# downmixersB.net
KiCad netlist of a schematic drawn in Altium Designer
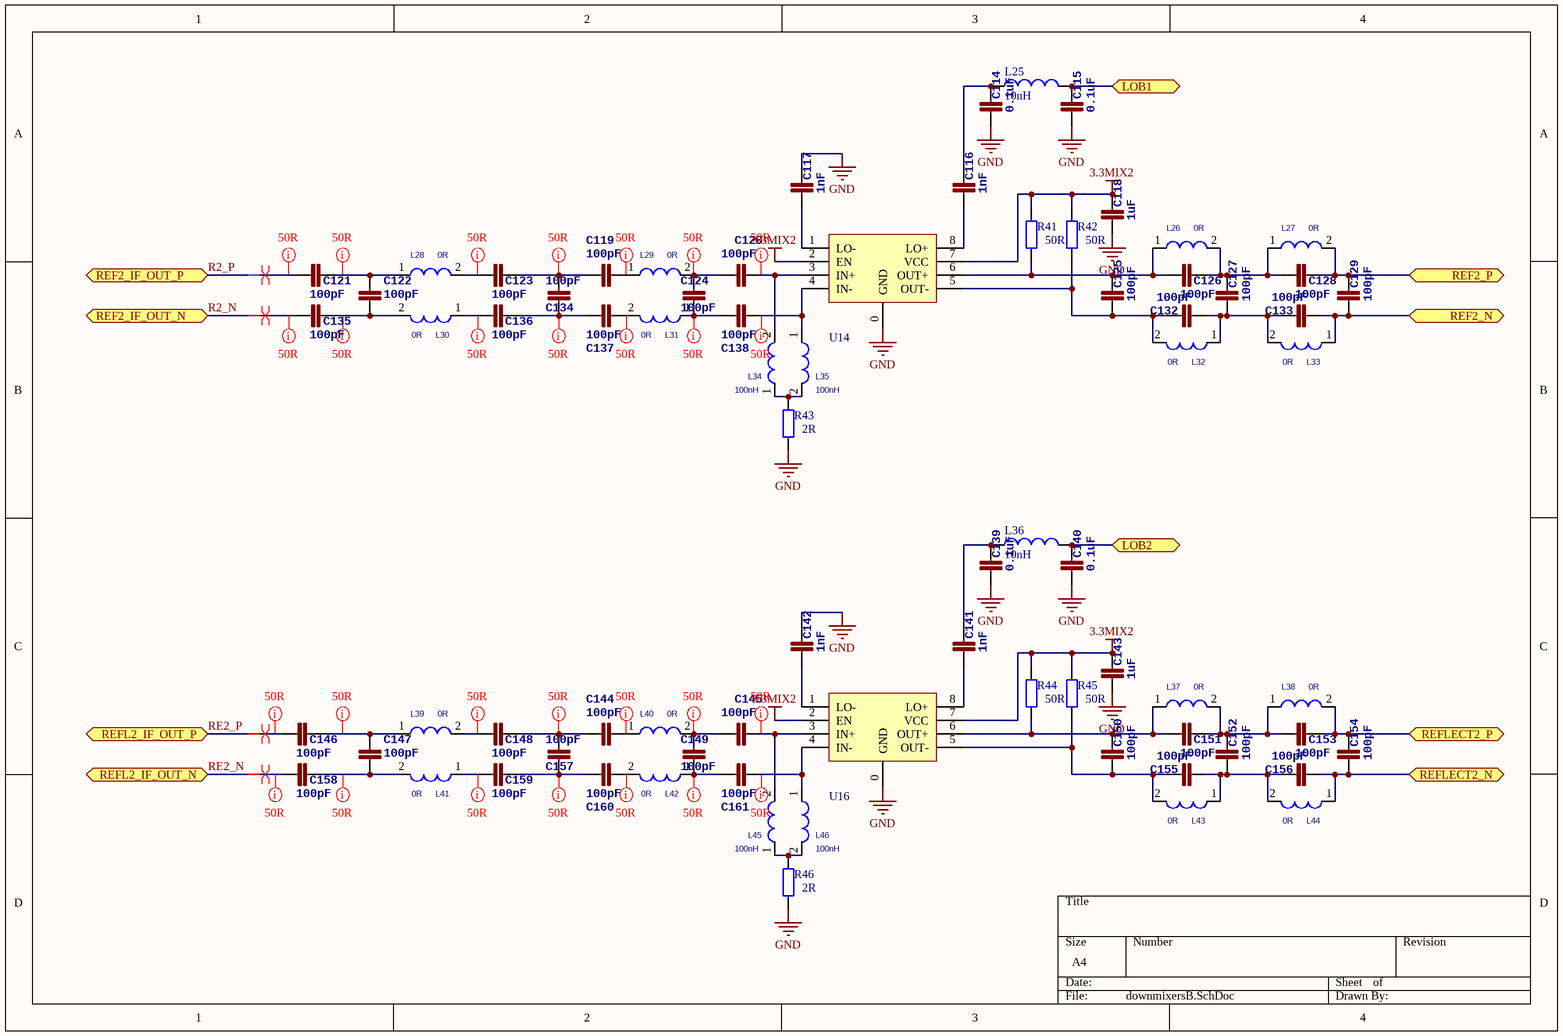
[diagram p0: downmixersB.SchDoc]

(export (version "E")
  (design (tool "Eeschema 10.0.6"))
  (components
    (comp (ref "C114")
      (value "0.1uF")
      (footprint "0402")
      (description "<b>Capacitor</b>\nStandard 0603 ceramic capacitor, and 0.1\" leaded capacitor.")
      (fields (field (name "PARTNO") "CC0402ZRY5V7BB104"))
      (libsource (lib "pixhawk2") (part "CAP0402-CAP"))
    )
    (comp (ref "C115")
      (value "0.1uF")
      (footprint "0402")
      (description "<b>Capacitor</b>\nStandard 0603 ceramic capacitor, and 0.1\" leaded capacitor.")
      (fields (field (name "PARTNO") "CC0402ZRY5V7BB104"))
      (libsource (lib "pixhawk2") (part "CAP0402-CAP"))
    )
    (comp (ref "C116")
      (value "1nF")
      (footprint "0402")
      (description "<b>Capacitor</b>\nStandard 0603 ceramic capacitor, and 0.1\" leaded capacitor.")
      (fields (field (name "PARTNO") "CC0402ZRY5V7BB104"))
      (libsource (lib "pixhawk2") (part "CAP0402-CAP"))
    )
    (comp (ref "C117")
      (value "1nF")
      (footprint "0402")
      (description "<b>Capacitor</b>\nStandard 0603 ceramic capacitor, and 0.1\" leaded capacitor.")
      (fields (field (name "PARTNO") "CC0402ZRY5V7BB104"))
      (libsource (lib "pixhawk2") (part "CAP0402-CAP"))
    )
    (comp (ref "C118")
      (value "1uF")
      (footprint "0402")
      (description "<b>Capacitor</b>\nStandard 0603 ceramic capacitor, and 0.1\" leaded capacitor.")
      (fields (field (name "PARTNO") "CC0402ZRY5V7BB104"))
      (libsource (lib "pixhawk2") (part "CAP0402-CAP"))
    )
    (comp (ref "C119")
      (value "100pF")
      (footprint "0402")
      (description "<b>Capacitor</b>\nStandard 0603 ceramic capacitor, and 0.1\" leaded capacitor.")
      (fields (field (name "PARTNO") "CC0402ZRY5V7BB104"))
      (libsource (lib "") (part "CAP0402-CAP_2"))
    )
    (comp (ref "C120")
      (value "100pF")
      (footprint "0402")
      (description "<b>Capacitor</b>\nStandard 0603 ceramic capacitor, and 0.1\" leaded capacitor.")
      (fields (field (name "PARTNO") "CC0402ZRY5V7BB104"))
      (libsource (lib "") (part "CAP0402-CAP_2"))
    )
    (comp (ref "C121")
      (value "100pF")
      (footprint "0402")
      (description "<b>Capacitor</b>\nStandard 0603 ceramic capacitor, and 0.1\" leaded capacitor.")
      (fields (field (name "PARTNO") "CC0402ZRY5V7BB104"))
      (libsource (lib "") (part "CAP0402-CAP_2"))
    )
    (comp (ref "C122")
      (value "100pF")
      (footprint "0402")
      (description "<b>Capacitor</b>\nStandard 0603 ceramic capacitor, and 0.1\" leaded capacitor.")
      (fields (field (name "PARTNO") "CC0402ZRY5V7BB104"))
      (libsource (lib "pixhawk2") (part "CAP0402-CAP"))
    )
    (comp (ref "C123")
      (value "100pF")
      (footprint "0402")
      (description "<b>Capacitor</b>\nStandard 0603 ceramic capacitor, and 0.1\" leaded capacitor.")
      (fields (field (name "PARTNO") "CC0402ZRY5V7BB104"))
      (libsource (lib "") (part "CAP0402-CAP_2"))
    )
    (comp (ref "C124")
      (value "100pF")
      (footprint "0402")
      (description "<b>Capacitor</b>\nStandard 0603 ceramic capacitor, and 0.1\" leaded capacitor.")
      (fields (field (name "PARTNO") "CC0402ZRY5V7BB104"))
      (libsource (lib "pixhawk2") (part "CAP0402-CAP"))
    )
    (comp (ref "C125")
      (value "100pF")
      (footprint "0402")
      (description "<b>Capacitor</b>\nStandard 0603 ceramic capacitor, and 0.1\" leaded capacitor.")
      (fields (field (name "PARTNO") "CC0402ZRY5V7BB104"))
      (libsource (lib "pixhawk2") (part "CAP0402-CAP"))
    )
    (comp (ref "C126")
      (value "100pF")
      (footprint "0402")
      (description "<b>Capacitor</b>\nStandard 0603 ceramic capacitor, and 0.1\" leaded capacitor.")
      (fields (field (name "PARTNO") "CC0402ZRY5V7BB104"))
      (libsource (lib "") (part "CAP0402-CAP_2"))
    )
    (comp (ref "C127")
      (value "100pF")
      (footprint "0402")
      (description "<b>Capacitor</b>\nStandard 0603 ceramic capacitor, and 0.1\" leaded capacitor.")
      (fields (field (name "PARTNO") "CC0402ZRY5V7BB104"))
      (libsource (lib "pixhawk2") (part "CAP0402-CAP"))
    )
    (comp (ref "C128")
      (value "100pF")
      (footprint "0402")
      (description "<b>Capacitor</b>\nStandard 0603 ceramic capacitor, and 0.1\" leaded capacitor.")
      (fields (field (name "PARTNO") "CC0402ZRY5V7BB104"))
      (libsource (lib "") (part "CAP0402-CAP_2"))
    )
    (comp (ref "C129")
      (value "100pF")
      (footprint "0402")
      (description "<b>Capacitor</b>\nStandard 0603 ceramic capacitor, and 0.1\" leaded capacitor.")
      (fields (field (name "PARTNO") "CC0402ZRY5V7BB104"))
      (libsource (lib "pixhawk2") (part "CAP0402-CAP"))
    )
    (comp (ref "C132")
      (value "100pF")
      (footprint "0402")
      (description "<b>Capacitor</b>\nStandard 0603 ceramic capacitor, and 0.1\" leaded capacitor.")
      (fields (field (name "PARTNO") "CC0402ZRY5V7BB104"))
      (libsource (lib "") (part "CAP0402-CAP_3"))
    )
    (comp (ref "C133")
      (value "100pF")
      (footprint "0402")
      (description "<b>Capacitor</b>\nStandard 0603 ceramic capacitor, and 0.1\" leaded capacitor.")
      (fields (field (name "PARTNO") "CC0402ZRY5V7BB104"))
      (libsource (lib "") (part "CAP0402-CAP_3"))
    )
    (comp (ref "C134")
      (value "100pF")
      (footprint "0402")
      (description "<b>Capacitor</b>\nStandard 0603 ceramic capacitor, and 0.1\" leaded capacitor.")
      (fields (field (name "PARTNO") "CC0402ZRY5V7BB104"))
      (libsource (lib "") (part "CAP0402-CAP_1"))
    )
    (comp (ref "C135")
      (value "100pF")
      (footprint "0402")
      (description "<b>Capacitor</b>\nStandard 0603 ceramic capacitor, and 0.1\" leaded capacitor.")
      (fields (field (name "PARTNO") "CC0402ZRY5V7BB104"))
      (libsource (lib "") (part "CAP0402-CAP_2"))
    )
    (comp (ref "C136")
      (value "100pF")
      (footprint "0402")
      (description "<b>Capacitor</b>\nStandard 0603 ceramic capacitor, and 0.1\" leaded capacitor.")
      (fields (field (name "PARTNO") "CC0402ZRY5V7BB104"))
      (libsource (lib "") (part "CAP0402-CAP_2"))
    )
    (comp (ref "C137")
      (value "100pF")
      (footprint "0402")
      (description "<b>Capacitor</b>\nStandard 0603 ceramic capacitor, and 0.1\" leaded capacitor.")
      (fields (field (name "PARTNO") "CC0402ZRY5V7BB104"))
      (libsource (lib "") (part "CAP0402-CAP_3"))
    )
    (comp (ref "C138")
      (value "100pF")
      (footprint "0402")
      (description "<b>Capacitor</b>\nStandard 0603 ceramic capacitor, and 0.1\" leaded capacitor.")
      (fields (field (name "PARTNO") "CC0402ZRY5V7BB104"))
      (libsource (lib "") (part "CAP0402-CAP_3"))
    )
    (comp (ref "C139")
      (value "0.1uF")
      (footprint "0402")
      (description "<b>Capacitor</b>\nStandard 0603 ceramic capacitor, and 0.1\" leaded capacitor.")
      (fields (field (name "PARTNO") "CC0402ZRY5V7BB104"))
      (libsource (lib "pixhawk2") (part "CAP0402-CAP"))
    )
    (comp (ref "C140")
      (value "0.1uF")
      (footprint "0402")
      (description "<b>Capacitor</b>\nStandard 0603 ceramic capacitor, and 0.1\" leaded capacitor.")
      (fields (field (name "PARTNO") "CC0402ZRY5V7BB104"))
      (libsource (lib "pixhawk2") (part "CAP0402-CAP"))
    )
    (comp (ref "C141")
      (value "1nF")
      (footprint "0402")
      (description "<b>Capacitor</b>\nStandard 0603 ceramic capacitor, and 0.1\" leaded capacitor.")
      (fields (field (name "PARTNO") "CC0402ZRY5V7BB104"))
      (libsource (lib "pixhawk2") (part "CAP0402-CAP"))
    )
    (comp (ref "C142")
      (value "1nF")
      (footprint "0402")
      (description "<b>Capacitor</b>\nStandard 0603 ceramic capacitor, and 0.1\" leaded capacitor.")
      (fields (field (name "PARTNO") "CC0402ZRY5V7BB104"))
      (libsource (lib "pixhawk2") (part "CAP0402-CAP"))
    )
    (comp (ref "C143")
      (value "1uF")
      (footprint "0402")
      (description "<b>Capacitor</b>\nStandard 0603 ceramic capacitor, and 0.1\" leaded capacitor.")
      (fields (field (name "PARTNO") "CC0402ZRY5V7BB104"))
      (libsource (lib "pixhawk2") (part "CAP0402-CAP"))
    )
    (comp (ref "C144")
      (value "100pF")
      (footprint "0402")
      (description "<b>Capacitor</b>\nStandard 0603 ceramic capacitor, and 0.1\" leaded capacitor.")
      (fields (field (name "PARTNO") "CC0402ZRY5V7BB104"))
      (libsource (lib "") (part "CAP0402-CAP_2"))
    )
    (comp (ref "C145")
      (value "100pF")
      (footprint "0402")
      (description "<b>Capacitor</b>\nStandard 0603 ceramic capacitor, and 0.1\" leaded capacitor.")
      (fields (field (name "PARTNO") "CC0402ZRY5V7BB104"))
      (libsource (lib "") (part "CAP0402-CAP_2"))
    )
    (comp (ref "C146")
      (value "100pF")
      (footprint "0402")
      (description "<b>Capacitor</b>\nStandard 0603 ceramic capacitor, and 0.1\" leaded capacitor.")
      (fields (field (name "PARTNO") "CC0402ZRY5V7BB104"))
      (libsource (lib "") (part "CAP0402-CAP_2"))
    )
    (comp (ref "C147")
      (value "100pF")
      (footprint "0402")
      (description "<b>Capacitor</b>\nStandard 0603 ceramic capacitor, and 0.1\" leaded capacitor.")
      (fields (field (name "PARTNO") "CC0402ZRY5V7BB104"))
      (libsource (lib "pixhawk2") (part "CAP0402-CAP"))
    )
    (comp (ref "C148")
      (value "100pF")
      (footprint "0402")
      (description "<b>Capacitor</b>\nStandard 0603 ceramic capacitor, and 0.1\" leaded capacitor.")
      (fields (field (name "PARTNO") "CC0402ZRY5V7BB104"))
      (libsource (lib "") (part "CAP0402-CAP_2"))
    )
    (comp (ref "C149")
      (value "100pF")
      (footprint "0402")
      (description "<b>Capacitor</b>\nStandard 0603 ceramic capacitor, and 0.1\" leaded capacitor.")
      (fields (field (name "PARTNO") "CC0402ZRY5V7BB104"))
      (libsource (lib "pixhawk2") (part "CAP0402-CAP"))
    )
    (comp (ref "C150")
      (value "100pF")
      (footprint "0402")
      (description "<b>Capacitor</b>\nStandard 0603 ceramic capacitor, and 0.1\" leaded capacitor.")
      (fields (field (name "PARTNO") "CC0402ZRY5V7BB104"))
      (libsource (lib "pixhawk2") (part "CAP0402-CAP"))
    )
    (comp (ref "C151")
      (value "100pF")
      (footprint "0402")
      (description "<b>Capacitor</b>\nStandard 0603 ceramic capacitor, and 0.1\" leaded capacitor.")
      (fields (field (name "PARTNO") "CC0402ZRY5V7BB104"))
      (libsource (lib "") (part "CAP0402-CAP_2"))
    )
    (comp (ref "C152")
      (value "100pF")
      (footprint "0402")
      (description "<b>Capacitor</b>\nStandard 0603 ceramic capacitor, and 0.1\" leaded capacitor.")
      (fields (field (name "PARTNO") "CC0402ZRY5V7BB104"))
      (libsource (lib "pixhawk2") (part "CAP0402-CAP"))
    )
    (comp (ref "C153")
      (value "100pF")
      (footprint "0402")
      (description "<b>Capacitor</b>\nStandard 0603 ceramic capacitor, and 0.1\" leaded capacitor.")
      (fields (field (name "PARTNO") "CC0402ZRY5V7BB104"))
      (libsource (lib "") (part "CAP0402-CAP_2"))
    )
    (comp (ref "C154")
      (value "100pF")
      (footprint "0402")
      (description "<b>Capacitor</b>\nStandard 0603 ceramic capacitor, and 0.1\" leaded capacitor.")
      (fields (field (name "PARTNO") "CC0402ZRY5V7BB104"))
      (libsource (lib "pixhawk2") (part "CAP0402-CAP"))
    )
    (comp (ref "C155")
      (value "100pF")
      (footprint "0402")
      (description "<b>Capacitor</b>\nStandard 0603 ceramic capacitor, and 0.1\" leaded capacitor.")
      (fields (field (name "PARTNO") "CC0402ZRY5V7BB104"))
      (libsource (lib "") (part "CAP0402-CAP_3"))
    )
    (comp (ref "C156")
      (value "100pF")
      (footprint "0402")
      (description "<b>Capacitor</b>\nStandard 0603 ceramic capacitor, and 0.1\" leaded capacitor.")
      (fields (field (name "PARTNO") "CC0402ZRY5V7BB104"))
      (libsource (lib "") (part "CAP0402-CAP_3"))
    )
    (comp (ref "C157")
      (value "100pF")
      (footprint "0402")
      (description "<b>Capacitor</b>\nStandard 0603 ceramic capacitor, and 0.1\" leaded capacitor.")
      (fields (field (name "PARTNO") "CC0402ZRY5V7BB104"))
      (libsource (lib "") (part "CAP0402-CAP_1"))
    )
    (comp (ref "C158")
      (value "100pF")
      (footprint "0402")
      (description "<b>Capacitor</b>\nStandard 0603 ceramic capacitor, and 0.1\" leaded capacitor.")
      (fields (field (name "PARTNO") "CC0402ZRY5V7BB104"))
      (libsource (lib "") (part "CAP0402-CAP_2"))
    )
    (comp (ref "C159")
      (value "100pF")
      (footprint "0402")
      (description "<b>Capacitor</b>\nStandard 0603 ceramic capacitor, and 0.1\" leaded capacitor.")
      (fields (field (name "PARTNO") "CC0402ZRY5V7BB104"))
      (libsource (lib "") (part "CAP0402-CAP_2"))
    )
    (comp (ref "C160")
      (value "100pF")
      (footprint "0402")
      (description "<b>Capacitor</b>\nStandard 0603 ceramic capacitor, and 0.1\" leaded capacitor.")
      (fields (field (name "PARTNO") "CC0402ZRY5V7BB104"))
      (libsource (lib "") (part "CAP0402-CAP_3"))
    )
    (comp (ref "C161")
      (value "100pF")
      (footprint "0402")
      (description "<b>Capacitor</b>\nStandard 0603 ceramic capacitor, and 0.1\" leaded capacitor.")
      (fields (field (name "PARTNO") "CC0402ZRY5V7BB104"))
      (libsource (lib "") (part "CAP0402-CAP_3"))
    )
    (comp (ref "L25")
      (value "10nH")
      (footprint "0402")
      (description "Inductor")
      (fields (field (name "PUBLISHER") "Altium Limited"))
      (libsource (lib "Miscellaneous Devices") (part "Inductor"))
    )
    (comp (ref "L26") (value "0R") (footprint "0805") (libsource (lib "*") (part "L/2.5*2.0")))
    (comp (ref "L27") (value "0R") (footprint "0805") (libsource (lib "*") (part "L/2.5*2.0")))
    (comp (ref "L28") (value "0R") (footprint "0805") (libsource (lib "*") (part "L/2.5*2.0")))
    (comp (ref "L29") (value "0R") (footprint "0805") (libsource (lib "*") (part "L/2.5*2.0")))
    (comp (ref "L30") (value "0R") (footprint "0805") (libsource (lib "*") (part "L/2.5*2.0")))
    (comp (ref "L31") (value "0R") (footprint "0805") (libsource (lib "*") (part "L/2.5*2.0")))
    (comp (ref "L32") (value "0R") (footprint "0805") (libsource (lib "*") (part "L/2.5*2.0")))
    (comp (ref "L33") (value "0R") (footprint "0805") (libsource (lib "*") (part "L/2.5*2.0")))
    (comp (ref "L34") (value "100nH") (footprint "0402") (libsource (lib "*") (part "L/2.5*2.0")))
    (comp (ref "L35") (value "100nH") (footprint "0402") (libsource (lib "*") (part "L/2.5*2.0")))
    (comp (ref "L36")
      (value "10nH")
      (footprint "0402")
      (description "Inductor")
      (fields (field (name "PUBLISHER") "Altium Limited"))
      (libsource (lib "Miscellaneous Devices") (part "Inductor"))
    )
    (comp (ref "L37") (value "0R") (footprint "0805") (libsource (lib "*") (part "L/2.5*2.0")))
    (comp (ref "L38") (value "0R") (footprint "0805") (libsource (lib "*") (part "L/2.5*2.0")))
    (comp (ref "L39") (value "0R") (footprint "0805") (libsource (lib "*") (part "L/2.5*2.0")))
    (comp (ref "L40") (value "0R") (footprint "0805") (libsource (lib "*") (part "L/2.5*2.0")))
    (comp (ref "L41") (value "0R") (footprint "0805") (libsource (lib "*") (part "L/2.5*2.0")))
    (comp (ref "L42") (value "0R") (footprint "0805") (libsource (lib "*") (part "L/2.5*2.0")))
    (comp (ref "L43") (value "0R") (footprint "0805") (libsource (lib "*") (part "L/2.5*2.0")))
    (comp (ref "L44") (value "0R") (footprint "0805") (libsource (lib "*") (part "L/2.5*2.0")))
    (comp (ref "L45") (value "100nH") (footprint "0402") (libsource (lib "*") (part "L/2.5*2.0")))
    (comp (ref "L46") (value "100nH") (footprint "0402") (libsource (lib "*") (part "L/2.5*2.0")))
    (comp (ref "R41")
      (value "50R")
      (footprint "0402")
      (description "Resistor")
      (libsource (lib "RTC6705") (part "Res2"))
    )
    (comp (ref "R42")
      (value "50R")
      (footprint "0402")
      (description "Resistor")
      (libsource (lib "RTC6705") (part "Res2"))
    )
    (comp (ref "R43")
      (value "2R")
      (footprint "0402")
      (description "Resistor")
      (libsource (lib "RTC6705") (part "Res2"))
    )
    (comp (ref "R44")
      (value "50R")
      (footprint "0402")
      (description "Resistor")
      (libsource (lib "RTC6705") (part "Res2"))
    )
    (comp (ref "R45")
      (value "50R")
      (footprint "0402")
      (description "Resistor")
      (libsource (lib "RTC6705") (part "Res2"))
    )
    (comp (ref "R46")
      (value "2R")
      (footprint "0402")
      (description "Resistor")
      (libsource (lib "RTC6705") (part "Res2"))
    )
    (comp (ref "U14") (value "LT5560") (footprint "LT5560") (libsource (lib "F4SDR") (part "LT5560")))
    (comp (ref "U16") (value "LT5560") (footprint "LT5560") (libsource (lib "F4SDR") (part "LT5560")))
  )
  (nets
    (net (code "1") (name "/LOB1") (class "Default")
      (node (ref "C115") (pin "2") (pinfunction "2_2") (pintype "passive"))
      (node (ref "L25") (pin "2") (pinfunction "2_2") (pintype "passive"))
    )
    (net (code "2") (name "/LOB2") (class "Default")
      (node (ref "C140") (pin "2") (pinfunction "2_2") (pintype "passive"))
      (node (ref "L36") (pin "2") (pinfunction "2_2") (pintype "passive"))
    )
    (net (code "3") (name "/R2_N") (class "Default")
      (node (ref "C135") (pin "1") (pinfunction "1_1") (pintype "passive"))
    )
    (net (code "4") (name "/R2_P") (class "Default")
      (node (ref "C121") (pin "1") (pinfunction "1_1") (pintype "passive"))
    )
    (net (code "5") (name "/RE2_N") (class "Default")
      (node (ref "C158") (pin "1") (pinfunction "1_1") (pintype "passive"))
    )
    (net (code "6") (name "/RE2_P") (class "Default")
      (node (ref "C146") (pin "1") (pinfunction "1_1") (pintype "passive"))
    )
    (net (code "7") (name "/REF2_N") (class "Default")
      (node (ref "C129") (pin "1") (pinfunction "1_1") (pintype "passive"))
      (node (ref "C133") (pin "1") (pinfunction "1_1") (pintype "passive"))
      (node (ref "L33") (pin "1") (pinfunction "1_1") (pintype "passive"))
    )
    (net (code "8") (name "/REF2_P") (class "Default")
      (node (ref "C128") (pin "2") (pinfunction "2_2") (pintype "passive"))
      (node (ref "C129") (pin "2") (pinfunction "2_2") (pintype "passive"))
      (node (ref "L27") (pin "2") (pinfunction "2_2") (pintype "passive"))
    )
    (net (code "9") (name "/REFLECT2_N") (class "Default")
      (node (ref "C154") (pin "1") (pinfunction "1_1") (pintype "passive"))
      (node (ref "C156") (pin "1") (pinfunction "1_1") (pintype "passive"))
      (node (ref "L44") (pin "1") (pinfunction "1_1") (pintype "passive"))
    )
    (net (code "10") (name "/REFLECT2_P") (class "Default")
      (node (ref "C153") (pin "2") (pinfunction "2_2") (pintype "passive"))
      (node (ref "C154") (pin "2") (pinfunction "2_2") (pintype "passive"))
      (node (ref "L38") (pin "2") (pinfunction "2_2") (pintype "passive"))
    )
    (net (code "11") (name "3.3MIX2") (class "Default")
      (node (ref "C118") (pin "2") (pinfunction "2_2") (pintype "passive"))
      (node (ref "C143") (pin "2") (pinfunction "2_2") (pintype "passive"))
      (node (ref "R41") (pin "2") (pinfunction "2_2") (pintype "passive"))
      (node (ref "R42") (pin "2") (pinfunction "2_2") (pintype "passive"))
      (node (ref "R44") (pin "2") (pinfunction "2_2") (pintype "passive"))
      (node (ref "R45") (pin "2") (pinfunction "2_2") (pintype "passive"))
      (node (ref "U14") (pin "2") (pinfunction "EN_2") (pintype "passive"))
      (node (ref "U14") (pin "7") (pinfunction "VCC_7") (pintype "passive"))
      (node (ref "U16") (pin "2") (pinfunction "EN_2") (pintype "passive"))
      (node (ref "U16") (pin "7") (pinfunction "VCC_7") (pintype "passive"))
    )
    (net (code "12") (name "GND") (class "Default")
      (node (ref "C114") (pin "1") (pinfunction "1_1") (pintype "passive"))
      (node (ref "C115") (pin "1") (pinfunction "1_1") (pintype "passive"))
      (node (ref "C117") (pin "2") (pinfunction "2_2") (pintype "passive"))
      (node (ref "C118") (pin "1") (pinfunction "1_1") (pintype "passive"))
      (node (ref "C139") (pin "1") (pinfunction "1_1") (pintype "passive"))
      (node (ref "C140") (pin "1") (pinfunction "1_1") (pintype "passive"))
      (node (ref "C142") (pin "2") (pinfunction "2_2") (pintype "passive"))
      (node (ref "C143") (pin "1") (pinfunction "1_1") (pintype "passive"))
      (node (ref "R43") (pin "1") (pinfunction "1_1") (pintype "passive"))
      (node (ref "R46") (pin "1") (pinfunction "1_1") (pintype "passive"))
      (node (ref "U14") (pin "0") (pinfunction "GND_0") (pintype "passive"))
      (node (ref "U16") (pin "0") (pinfunction "GND_0") (pintype "passive"))
    )
    (net (code "13") (name "Net-(C114-Pad2)") (class "Default")
      (node (ref "C114") (pin "2") (pinfunction "2_2") (pintype "passive"))
      (node (ref "C116") (pin "2") (pinfunction "2_2") (pintype "passive"))
      (node (ref "L25") (pin "1") (pinfunction "1_1") (pintype "passive"))
    )
    (net (code "14") (name "Net-(C119-Pad1)") (class "Default")
      (node (ref "C119") (pin "1") (pinfunction "1_1") (pintype "passive"))
      (node (ref "C123") (pin "2") (pinfunction "2_2") (pintype "passive"))
      (node (ref "C134") (pin "1") (pinfunction "1_1") (pintype "passive"))
    )
    (net (code "15") (name "Net-(C119-Pad2)") (class "Default")
      (node (ref "C119") (pin "2") (pinfunction "2_2") (pintype "passive"))
      (node (ref "L29") (pin "1") (pinfunction "1_1") (pintype "passive"))
    )
    (net (code "16") (name "Net-(C120-Pad1)") (class "Default")
      (node (ref "C120") (pin "1") (pinfunction "1_1") (pintype "passive"))
      (node (ref "C124") (pin "2") (pinfunction "2_2") (pintype "passive"))
      (node (ref "L29") (pin "2") (pinfunction "2_2") (pintype "passive"))
    )
    (net (code "17") (name "Net-(C121-Pad2)") (class "Default")
      (node (ref "C121") (pin "2") (pinfunction "2_2") (pintype "passive"))
      (node (ref "C122") (pin "2") (pinfunction "2_2") (pintype "passive"))
      (node (ref "L28") (pin "1") (pinfunction "1_1") (pintype "passive"))
    )
    (net (code "18") (name "Net-(C122-Pad1)") (class "Default")
      (node (ref "C122") (pin "1") (pinfunction "1_1") (pintype "passive"))
      (node (ref "C135") (pin "2") (pinfunction "2_2") (pintype "passive"))
      (node (ref "L30") (pin "2") (pinfunction "2_2") (pintype "passive"))
    )
    (net (code "19") (name "Net-(C123-Pad1)") (class "Default")
      (node (ref "C123") (pin "1") (pinfunction "1_1") (pintype "passive"))
      (node (ref "L28") (pin "2") (pinfunction "2_2") (pintype "passive"))
    )
    (net (code "20") (name "Net-(C124-Pad1)") (class "Default")
      (node (ref "C124") (pin "1") (pinfunction "1_1") (pintype "passive"))
      (node (ref "C138") (pin "2") (pinfunction "2_2") (pintype "passive"))
      (node (ref "L31") (pin "1") (pinfunction "1_1") (pintype "passive"))
    )
    (net (code "21") (name "Net-(C126-Pad2)") (class "Default")
      (node (ref "C126") (pin "2") (pinfunction "2_2") (pintype "passive"))
      (node (ref "C127") (pin "2") (pinfunction "2_2") (pintype "passive"))
      (node (ref "C128") (pin "1") (pinfunction "1_1") (pintype "passive"))
      (node (ref "L26") (pin "2") (pinfunction "2_2") (pintype "passive"))
      (node (ref "L27") (pin "1") (pinfunction "1_1") (pintype "passive"))
    )
    (net (code "22") (name "Net-(C127-Pad1)") (class "Default")
      (node (ref "C127") (pin "1") (pinfunction "1_1") (pintype "passive"))
      (node (ref "C132") (pin "1") (pinfunction "1_1") (pintype "passive"))
      (node (ref "C133") (pin "2") (pinfunction "2_2") (pintype "passive"))
      (node (ref "L32") (pin "1") (pinfunction "1_1") (pintype "passive"))
      (node (ref "L33") (pin "2") (pinfunction "2_2") (pintype "passive"))
    )
    (net (code "23") (name "Net-(C134-Pad2)") (class "Default")
      (node (ref "C134") (pin "2") (pinfunction "2_2") (pintype "passive"))
      (node (ref "C136") (pin "2") (pinfunction "2_2") (pintype "passive"))
      (node (ref "C137") (pin "2") (pinfunction "2_2") (pintype "passive"))
    )
    (net (code "24") (name "Net-(C136-Pad1)") (class "Default")
      (node (ref "C136") (pin "1") (pinfunction "1_1") (pintype "passive"))
      (node (ref "L30") (pin "1") (pinfunction "1_1") (pintype "passive"))
    )
    (net (code "25") (name "Net-(C137-Pad1)") (class "Default")
      (node (ref "C137") (pin "1") (pinfunction "1_1") (pintype "passive"))
      (node (ref "L31") (pin "2") (pinfunction "2_2") (pintype "passive"))
    )
    (net (code "26") (name "Net-(C139-Pad2)") (class "Default")
      (node (ref "C139") (pin "2") (pinfunction "2_2") (pintype "passive"))
      (node (ref "C141") (pin "2") (pinfunction "2_2") (pintype "passive"))
      (node (ref "L36") (pin "1") (pinfunction "1_1") (pintype "passive"))
    )
    (net (code "27") (name "Net-(C144-Pad1)") (class "Default")
      (node (ref "C144") (pin "1") (pinfunction "1_1") (pintype "passive"))
      (node (ref "C148") (pin "2") (pinfunction "2_2") (pintype "passive"))
      (node (ref "C157") (pin "1") (pinfunction "1_1") (pintype "passive"))
    )
    (net (code "28") (name "Net-(C144-Pad2)") (class "Default")
      (node (ref "C144") (pin "2") (pinfunction "2_2") (pintype "passive"))
      (node (ref "L40") (pin "1") (pinfunction "1_1") (pintype "passive"))
    )
    (net (code "29") (name "Net-(C145-Pad1)") (class "Default")
      (node (ref "C145") (pin "1") (pinfunction "1_1") (pintype "passive"))
      (node (ref "C149") (pin "2") (pinfunction "2_2") (pintype "passive"))
      (node (ref "L40") (pin "2") (pinfunction "2_2") (pintype "passive"))
    )
    (net (code "30") (name "Net-(C146-Pad2)") (class "Default")
      (node (ref "C146") (pin "2") (pinfunction "2_2") (pintype "passive"))
      (node (ref "C147") (pin "2") (pinfunction "2_2") (pintype "passive"))
      (node (ref "L39") (pin "1") (pinfunction "1_1") (pintype "passive"))
    )
    (net (code "31") (name "Net-(C147-Pad1)") (class "Default")
      (node (ref "C147") (pin "1") (pinfunction "1_1") (pintype "passive"))
      (node (ref "C158") (pin "2") (pinfunction "2_2") (pintype "passive"))
      (node (ref "L41") (pin "2") (pinfunction "2_2") (pintype "passive"))
    )
    (net (code "32") (name "Net-(C148-Pad1)") (class "Default")
      (node (ref "C148") (pin "1") (pinfunction "1_1") (pintype "passive"))
      (node (ref "L39") (pin "2") (pinfunction "2_2") (pintype "passive"))
    )
    (net (code "33") (name "Net-(C149-Pad1)") (class "Default")
      (node (ref "C149") (pin "1") (pinfunction "1_1") (pintype "passive"))
      (node (ref "C161") (pin "2") (pinfunction "2_2") (pintype "passive"))
      (node (ref "L42") (pin "1") (pinfunction "1_1") (pintype "passive"))
    )
    (net (code "34") (name "Net-(C151-Pad2)") (class "Default")
      (node (ref "C151") (pin "2") (pinfunction "2_2") (pintype "passive"))
      (node (ref "C152") (pin "2") (pinfunction "2_2") (pintype "passive"))
      (node (ref "C153") (pin "1") (pinfunction "1_1") (pintype "passive"))
      (node (ref "L37") (pin "2") (pinfunction "2_2") (pintype "passive"))
      (node (ref "L38") (pin "1") (pinfunction "1_1") (pintype "passive"))
    )
    (net (code "35") (name "Net-(C152-Pad1)") (class "Default")
      (node (ref "C152") (pin "1") (pinfunction "1_1") (pintype "passive"))
      (node (ref "C155") (pin "1") (pinfunction "1_1") (pintype "passive"))
      (node (ref "C156") (pin "2") (pinfunction "2_2") (pintype "passive"))
      (node (ref "L43") (pin "1") (pinfunction "1_1") (pintype "passive"))
      (node (ref "L44") (pin "2") (pinfunction "2_2") (pintype "passive"))
    )
    (net (code "36") (name "Net-(C157-Pad2)") (class "Default")
      (node (ref "C157") (pin "2") (pinfunction "2_2") (pintype "passive"))
      (node (ref "C159") (pin "2") (pinfunction "2_2") (pintype "passive"))
      (node (ref "C160") (pin "2") (pinfunction "2_2") (pintype "passive"))
    )
    (net (code "37") (name "Net-(C159-Pad1)") (class "Default")
      (node (ref "C159") (pin "1") (pinfunction "1_1") (pintype "passive"))
      (node (ref "L41") (pin "1") (pinfunction "1_1") (pintype "passive"))
    )
    (net (code "38") (name "Net-(C160-Pad1)") (class "Default")
      (node (ref "C160") (pin "1") (pinfunction "1_1") (pintype "passive"))
      (node (ref "L42") (pin "2") (pinfunction "2_2") (pintype "passive"))
    )
    (net (code "39") (name "Net-(L34-Pad1)") (class "Default")
      (node (ref "L34") (pin "1") (pinfunction "1_1") (pintype "passive"))
      (node (ref "L35") (pin "2") (pinfunction "2_2") (pintype "passive"))
      (node (ref "R43") (pin "2") (pinfunction "2_2") (pintype "passive"))
    )
    (net (code "40") (name "Net-(L45-Pad1)") (class "Default")
      (node (ref "L45") (pin "1") (pinfunction "1_1") (pintype "passive"))
      (node (ref "L46") (pin "2") (pinfunction "2_2") (pintype "passive"))
      (node (ref "R46") (pin "2") (pinfunction "2_2") (pintype "passive"))
    )
    (net (code "41") (name "Net-(U14-IN+)") (class "Default")
      (node (ref "C120") (pin "2") (pinfunction "2_2") (pintype "passive"))
      (node (ref "L34") (pin "2") (pinfunction "2_2") (pintype "passive"))
      (node (ref "U14") (pin "3") (pinfunction "IN+_3") (pintype "passive"))
    )
    (net (code "42") (name "Net-(U14-IN-)") (class "Default")
      (node (ref "C138") (pin "1") (pinfunction "1_1") (pintype "passive"))
      (node (ref "L35") (pin "1") (pinfunction "1_1") (pintype "passive"))
      (node (ref "U14") (pin "4") (pinfunction "IN-_4") (pintype "passive"))
    )
    (net (code "43") (name "Net-(U14-LO+)") (class "Default")
      (node (ref "C116") (pin "1") (pinfunction "1_1") (pintype "passive"))
      (node (ref "U14") (pin "8") (pinfunction "LO+_8") (pintype "passive"))
    )
    (net (code "44") (name "Net-(U14-LO-)") (class "Default")
      (node (ref "C117") (pin "1") (pinfunction "1_1") (pintype "passive"))
      (node (ref "U14") (pin "1") (pinfunction "LO-_1") (pintype "passive"))
    )
    (net (code "45") (name "Net-(U14-OUT+)") (class "Default")
      (node (ref "C125") (pin "2") (pinfunction "2_2") (pintype "passive"))
      (node (ref "C126") (pin "1") (pinfunction "1_1") (pintype "passive"))
      (node (ref "L26") (pin "1") (pinfunction "1_1") (pintype "passive"))
      (node (ref "R41") (pin "1") (pinfunction "1_1") (pintype "passive"))
      (node (ref "U14") (pin "6") (pinfunction "OUT+_6") (pintype "passive"))
    )
    (net (code "46") (name "Net-(U14-OUT-)") (class "Default")
      (node (ref "C125") (pin "1") (pinfunction "1_1") (pintype "passive"))
      (node (ref "C132") (pin "2") (pinfunction "2_2") (pintype "passive"))
      (node (ref "L32") (pin "2") (pinfunction "2_2") (pintype "passive"))
      (node (ref "R42") (pin "1") (pinfunction "1_1") (pintype "passive"))
      (node (ref "U14") (pin "5") (pinfunction "OUT-_5") (pintype "passive"))
    )
    (net (code "47") (name "Net-(U16-IN+)") (class "Default")
      (node (ref "C145") (pin "2") (pinfunction "2_2") (pintype "passive"))
      (node (ref "L45") (pin "2") (pinfunction "2_2") (pintype "passive"))
      (node (ref "U16") (pin "3") (pinfunction "IN+_3") (pintype "passive"))
    )
    (net (code "48") (name "Net-(U16-IN-)") (class "Default")
      (node (ref "C161") (pin "1") (pinfunction "1_1") (pintype "passive"))
      (node (ref "L46") (pin "1") (pinfunction "1_1") (pintype "passive"))
      (node (ref "U16") (pin "4") (pinfunction "IN-_4") (pintype "passive"))
    )
    (net (code "49") (name "Net-(U16-LO+)") (class "Default")
      (node (ref "C141") (pin "1") (pinfunction "1_1") (pintype "passive"))
      (node (ref "U16") (pin "8") (pinfunction "LO+_8") (pintype "passive"))
    )
    (net (code "50") (name "Net-(U16-LO-)") (class "Default")
      (node (ref "C142") (pin "1") (pinfunction "1_1") (pintype "passive"))
      (node (ref "U16") (pin "1") (pinfunction "LO-_1") (pintype "passive"))
    )
    (net (code "51") (name "Net-(U16-OUT+)") (class "Default")
      (node (ref "C150") (pin "2") (pinfunction "2_2") (pintype "passive"))
      (node (ref "C151") (pin "1") (pinfunction "1_1") (pintype "passive"))
      (node (ref "L37") (pin "1") (pinfunction "1_1") (pintype "passive"))
      (node (ref "R44") (pin "1") (pinfunction "1_1") (pintype "passive"))
      (node (ref "U16") (pin "6") (pinfunction "OUT+_6") (pintype "passive"))
    )
    (net (code "52") (name "Net-(U16-OUT-)") (class "Default")
      (node (ref "C150") (pin "1") (pinfunction "1_1") (pintype "passive"))
      (node (ref "C155") (pin "2") (pinfunction "2_2") (pintype "passive"))
      (node (ref "L43") (pin "2") (pinfunction "2_2") (pintype "passive"))
      (node (ref "R45") (pin "1") (pinfunction "1_1") (pintype "passive"))
      (node (ref "U16") (pin "5") (pinfunction "OUT-_5") (pintype "passive"))
    )
  )
)
